# Rectangular_Touch_Pad_V2_3.net
KiCad netlist of a schematic drawn in EAGLE
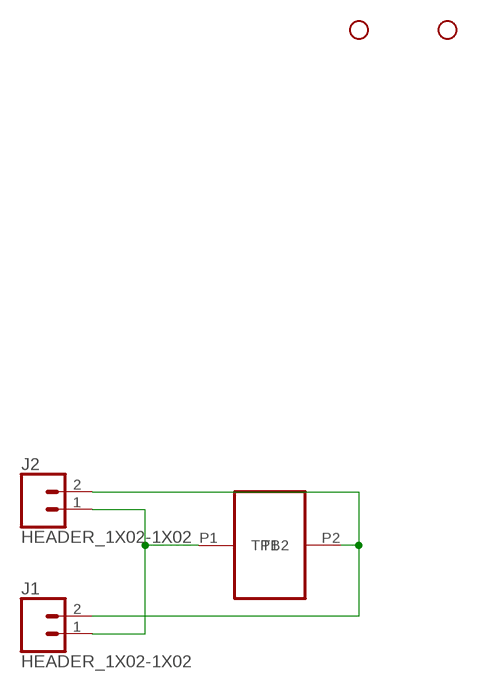
[diagram p0: schematic, sheet 1]

(export (version "E")
  (design (tool "Eeschema 10.0.6"))
  (components
    (comp (ref "H1")
      (value "STAND-OFF-")
      (footprint "eagle-import:STAND-OFF")
      (libsource (lib "eagle-import") (part "STAND-OFF-"))
    )
    (comp (ref "H2")
      (value "STAND-OFF-")
      (footprint "eagle-import:STAND-OFF")
      (libsource (lib "eagle-import") (part "STAND-OFF-"))
    )
    (comp (ref "J1")
      (value "HEADER_1X02-1X02")
      (footprint "eagle-import:1X02")
      (libsource (lib "eagle-import") (part "HEADER_1X02-1X02"))
    )
    (comp (ref "J2")
      (value "HEADER_1X02-1X02")
      (footprint "eagle-import:1X02")
      (libsource (lib "eagle-import") (part "HEADER_1X02-1X02"))
    )
    (comp (ref "U$1")
      (value "TOUCHPAD-VER2.3")
      (footprint "eagle-import:TOUCHPAD-RECT-VER2.3")
      (libsource (lib "eagle-import") (part "TOUCHPAD-VER2.3"))
    )
  )
  (nets
    (net (code "1") (name "Net-(U$1-TB2)") (class "Default")
      (node (ref "J1") (pin "2") (pinfunction "2_2") (pintype "passive"))
      (node (ref "J2") (pin "2") (pinfunction "2_2") (pintype "passive"))
      (node (ref "U$1") (pin "P2") (pinfunction "TB2_P2") (pintype "bidirectional"))
    )
    (net (code "2") (name "Net-(U$1-TP1)") (class "Default")
      (node (ref "J1") (pin "1") (pinfunction "1_1") (pintype "passive"))
      (node (ref "J2") (pin "1") (pinfunction "1_1") (pintype "passive"))
      (node (ref "U$1") (pin "P1") (pinfunction "TP1_P1") (pintype "bidirectional"))
    )
  )
)
